# ESP32_with_USBC.net
KiCad netlist of a schematic drawn in Altium Designer
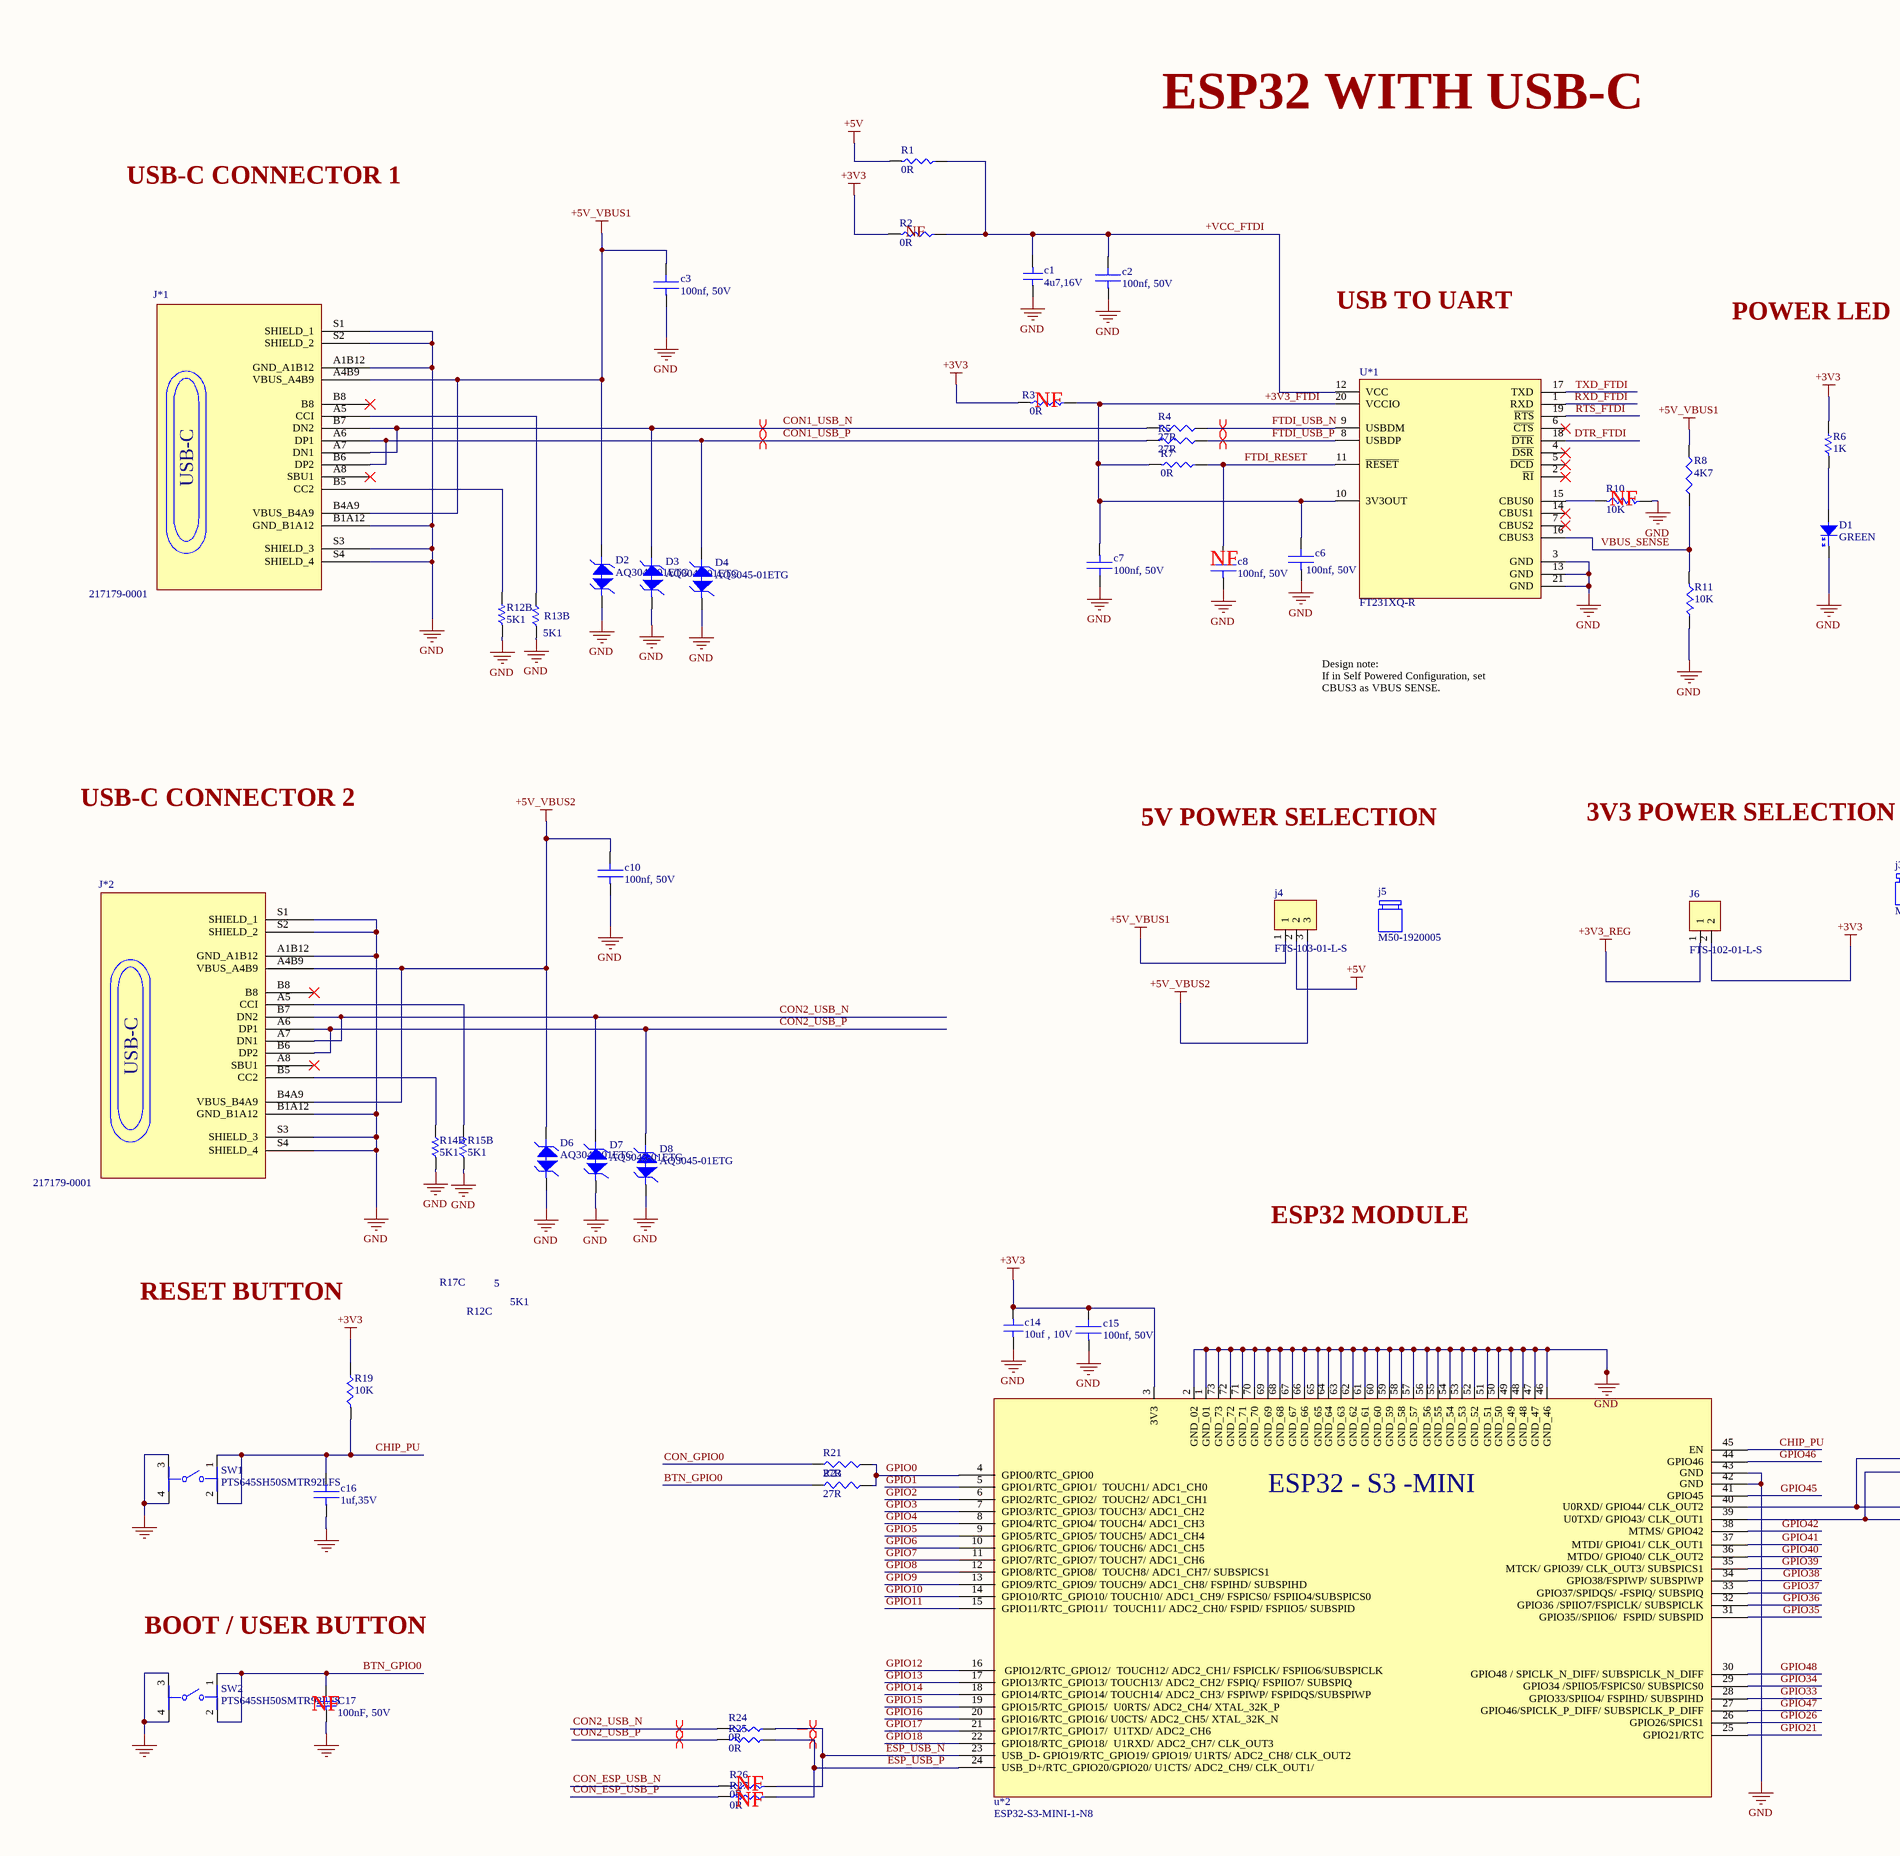
[diagram p0: ESP32 with USBC.SchDoc, left]
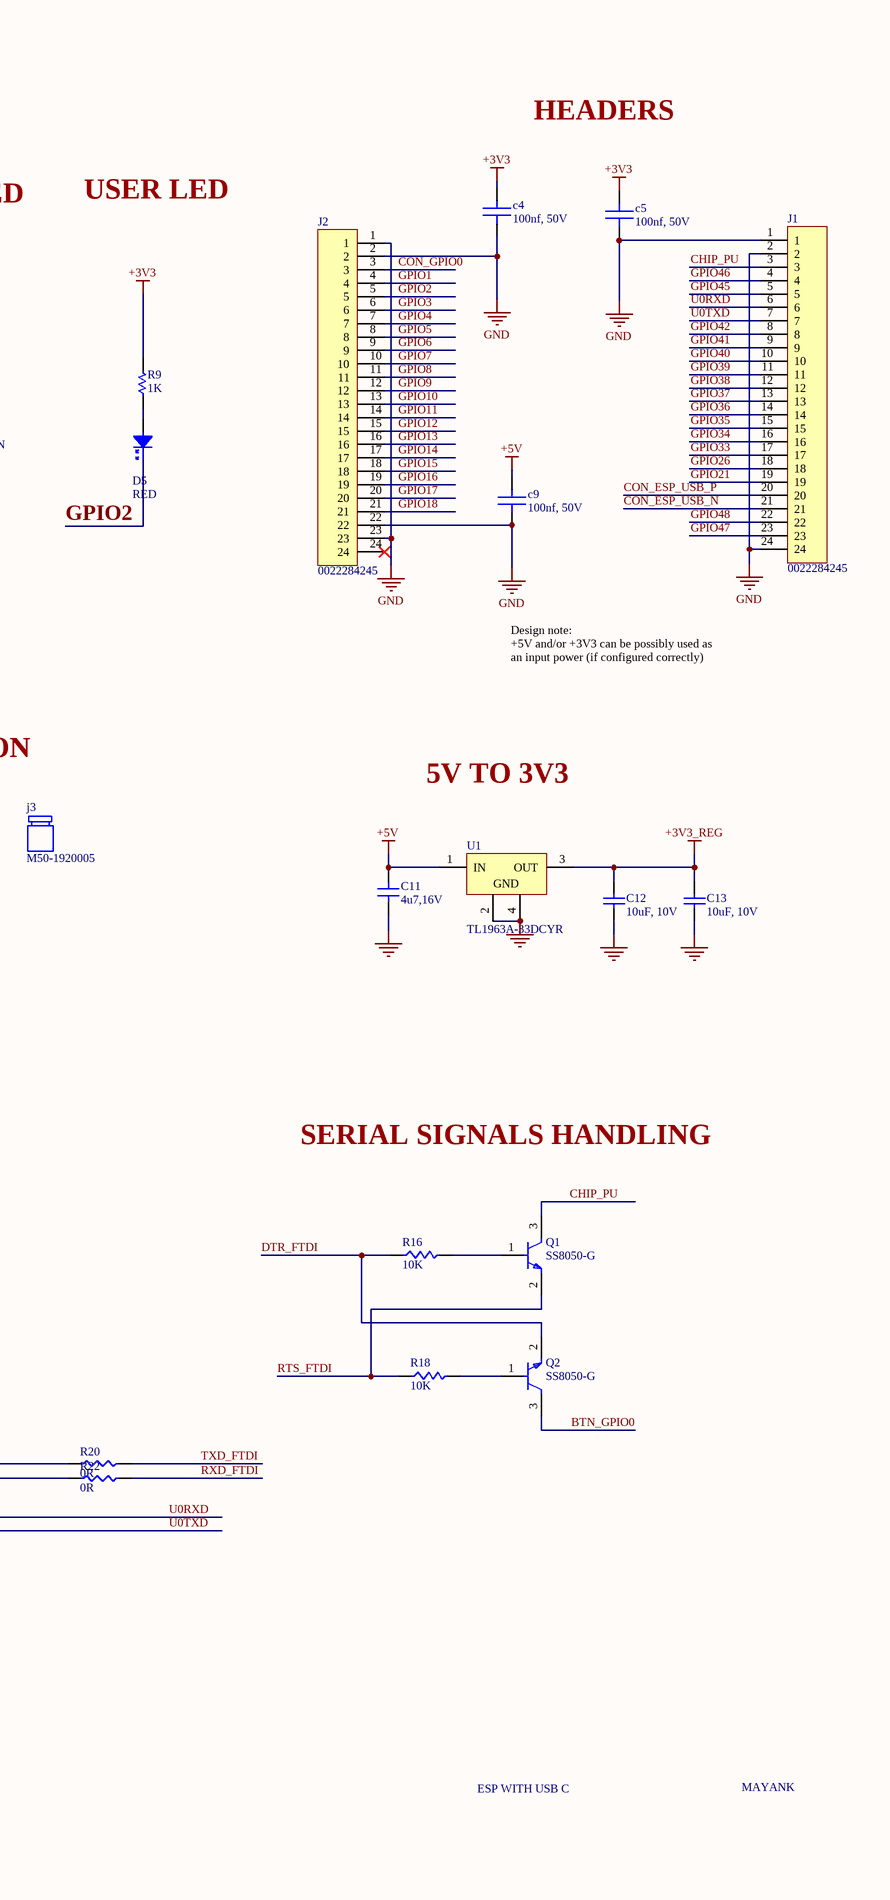
[diagram p1: ESP32 with USBC.SchDoc, right]

(export (version "E")
  (design (tool "Eeschema 10.0.6"))
  (components
    (comp (ref "c1")
      (value "4u7,16V")
      (footprint "CAPC1005X80N")
      (description "CAP CER 4.7UF 16V X5R 0402")
      (fields
        (field (name "MANUFACTURER") "Samsung Electro-Mechanics")
        (field (name "MANUFACTURER PART NUMBER") "CL05A475MO5NUNC")
      )
      (libsource (lib "Schlib1") (part "CL05A475MO5NUNC"))
    )
    (comp (ref "c2")
      (value "100nf, 50V")
      (footprint "CAPC1005X80N")
      (description "50V 100nF X7R 卤10% 0402 Multilayer Ceramic Capacitors MLCC - SMD/SMT ROHS")
      (fields
        (field (name "MANUFACTURER") "Samsung Electro-Mechanics")
        (field (name "MANUFACTURER PART NUMBER") "CL05B104KB5NNNC")
      )
      (libsource (lib "Schlib1") (part "CL05B104KB5NNNC"))
    )
    (comp (ref "c3")
      (value "100nf, 50V")
      (footprint "CAPC1005X80N")
      (description "50V 100nF X7R 卤10% 0402 Multilayer Ceramic Capacitors MLCC - SMD/SMT ROHS")
      (fields
        (field (name "MANUFACTURER") "Samsung Electro-Mechanics")
        (field (name "MANUFACTURER PART NUMBER") "CL05B104KB5NNNC")
      )
      (libsource (lib "Schlib1") (part "CL05B104KB5NNNC"))
    )
    (comp (ref "c4")
      (value "100nf, 50V")
      (footprint "CAPC1005X80N")
      (description "50V 100nF X7R 卤10% 0402 Multilayer Ceramic Capacitors MLCC - SMD/SMT ROHS")
      (fields
        (field (name "MANUFACTURER") "Samsung Electro-Mechanics")
        (field (name "MANUFACTURER PART NUMBER") "CL05B104KB5NNNC")
      )
      (libsource (lib "Schlib1") (part "CL05B104KB5NNNC"))
    )
    (comp (ref "c5")
      (value "100nf, 50V")
      (footprint "CAPC1005X80N")
      (description "50V 100nF X7R 卤10% 0402 Multilayer Ceramic Capacitors MLCC - SMD/SMT ROHS")
      (fields
        (field (name "MANUFACTURER") "Samsung Electro-Mechanics")
        (field (name "MANUFACTURER PART NUMBER") "CL05B104KB5NNNC")
      )
      (libsource (lib "Schlib1") (part "CL05B104KB5NNNC"))
    )
    (comp (ref "c6")
      (value "100nf, 50V")
      (footprint "CAPC1005X80N")
      (description "50V 100nF X7R 卤10% 0402 Multilayer Ceramic Capacitors MLCC - SMD/SMT ROHS")
      (fields
        (field (name "MANUFACTURER") "Samsung Electro-Mechanics")
        (field (name "MANUFACTURER PART NUMBER") "CL05B104KB5NNNC")
      )
      (libsource (lib "Schlib1") (part "CL05B104KB5NNNC"))
    )
    (comp (ref "c7")
      (value "100nf, 50V")
      (footprint "CAPC1005X80N")
      (description "50V 100nF X7R 卤10% 0402 Multilayer Ceramic Capacitors MLCC - SMD/SMT ROHS")
      (fields
        (field (name "MANUFACTURER") "Samsung Electro-Mechanics")
        (field (name "MANUFACTURER PART NUMBER") "CL05B104KB5NNNC")
      )
      (libsource (lib "Schlib1") (part "CL05B104KB5NNNC"))
    )
    (comp (ref "c8")
      (value "100nf, 50V")
      (footprint "CAPC1005X80N")
      (description "50V 100nF X7R 卤10% 0402 Multilayer Ceramic Capacitors MLCC - SMD/SMT ROHS")
      (fields
        (field (name "MANUFACTURER") "Samsung Electro-Mechanics")
        (field (name "MANUFACTURER PART NUMBER") "CL05B104KB5NNNC")
      )
      (libsource (lib "Schlib1") (part "CL05B104KB5NNNC"))
    )
    (comp (ref "c9")
      (value "100nf, 50V")
      (footprint "CAPC1005X80N")
      (description "50V 100nF X7R 卤10% 0402 Multilayer Ceramic Capacitors MLCC - SMD/SMT ROHS")
      (fields
        (field (name "MANUFACTURER") "Samsung Electro-Mechanics")
        (field (name "MANUFACTURER PART NUMBER") "CL05B104KB5NNNC")
      )
      (libsource (lib "Schlib1") (part "CL05B104KB5NNNC"))
    )
    (comp (ref "c10")
      (value "100nf, 50V")
      (footprint "CAPC1005X80N")
      (description "50V 100nF X7R 卤10% 0402 Multilayer Ceramic Capacitors MLCC - SMD/SMT ROHS")
      (fields
        (field (name "MANUFACTURER") "Samsung Electro-Mechanics")
        (field (name "MANUFACTURER PART NUMBER") "CL05B104KB5NNNC")
      )
      (libsource (lib "Schlib1") (part "CL05B104KB5NNNC"))
    )
    (comp (ref "C11")
      (value "4u7,16V")
      (footprint "CAPC1005X80N")
      (description "CAP CER 4.7UF 16V X5R 0402")
      (fields
        (field (name "MANUFACTURER") "Samsung Electro-Mechanics")
        (field (name "MANUFACTURER PART NUMBER") "CL05A475MO5NUNC")
      )
      (libsource (lib "Schlib1") (part "CL05A475MO5NUNC"))
    )
    (comp (ref "C12")
      (value "10uF, 10V")
      (footprint "CAPC1005X80N")
      (description "CAP CER 10UF 10V X5R 0402")
      (fields
        (field (name "MANUFACTURER") "Samsung")
        (field (name "MANUFACTURER PART NUMBER") "CL05A106MP8NUB8")
      )
      (libsource (lib "Schlib") (part "CL05A106MP8NUB8"))
    )
    (comp (ref "C13")
      (value "10uF, 10V")
      (footprint "CAPC1005X80N")
      (description "CAP CER 10UF 10V X5R 0402")
      (fields
        (field (name "MANUFACTURER") "Samsung")
        (field (name "MANUFACTURER PART NUMBER") "CL05A106MP8NUB8")
      )
      (libsource (lib "Schlib") (part "CL05A106MP8NUB8"))
    )
    (comp (ref "c14")
      (value "10uf , 10V")
      (footprint "CAPC1005X80N")
      (description "10V 10uF X5R 卤20% 0402 Multilayer Ceramic Capacitors MLCC - SMD/SMT ROHS")
      (fields
        (field (name "MANUFACTURER") "Samsung Electro-Mechanics")
        (field (name "MANUFACTURER PART NUMBER") "CL05A106MP6NUN8")
      )
      (libsource (lib "Schlib1") (part "CL05A106MP6NUN8"))
    )
    (comp (ref "c15")
      (value "100nf, 50V")
      (footprint "CAPC1005X80N")
      (description "50V 100nF X7R 卤10% 0402 Multilayer Ceramic Capacitors MLCC - SMD/SMT ROHS")
      (fields
        (field (name "MANUFACTURER") "Samsung Electro-Mechanics")
        (field (name "MANUFACTURER PART NUMBER") "CL05B104KB5NNNC")
      )
      (libsource (lib "Schlib1") (part "CL05B104KB5NNNC"))
    )
    (comp (ref "c16")
      (value "1uf,35V")
      (footprint "CAPC1005X80N")
      (description "CAP CER 1UF 35V X5R 0402")
      (fields
        (field (name "MANUFACTURER") "Samsung Electro-Mechanics")
        (field (name "MANUFACTURER PART NUMBER") "CL05A105KL5NRNC")
      )
      (libsource (lib "Schlib1") (part "CL05A105KL5NRNC"))
    )
    (comp (ref "C17")
      (value "100nF, 50V")
      (footprint "CAPC1005X80N")
      (description "CAP CER 0.1UF 50V X7R 0402")
      (fields
        (field (name "MANUFACTURER") "Samsung")
        (field (name "MANUFACTURER PART NUMBER") "CL05B104KB54PNC")
      )
      (libsource (lib "Schlib") (part "CL05B104KB54PNC"))
    )
    (comp (ref "D1")
      (value "GREEN")
      (footprint "LED0402G")
      (description "Chipled (0402) Truegreen Ultrabright -E4 ¦Vishay VLMTG1500-GS08")
      (fields
        (field (name "MANUFACTURER") "Vishay")
        (field (name "MANUFACTURER PART NUMBER") "VLMTG1500-GS08")
      )
      (libsource (lib "Schlib1") (part "VLMTG1500-GS08"))
    )
    (comp (ref "D2")
      (value "AQ3045-01ETG")
      (footprint "SOD882")
      (description "TVS DIODE 5.3VWM 12VC SOD882")
      (fields (field (name "MANUFACTURER") "Littelfuse") (field (name "LCSC PART NUMBER") "C3710326"))
      (libsource (lib "Schlib1") (part "AQ3045-01ETG"))
    )
    (comp (ref "D3")
      (value "AQ3045-01ETG")
      (footprint "SOD882")
      (description "TVS DIODE 5.3VWM 12VC SOD882")
      (fields (field (name "MANUFACTURER") "Littelfuse") (field (name "LCSC PART NUMBER") "C3710326"))
      (libsource (lib "Schlib1") (part "AQ3045-01ETG"))
    )
    (comp (ref "D4")
      (value "AQ3045-01ETG")
      (footprint "SOD882")
      (description "TVS DIODE 5.3VWM 12VC SOD882")
      (fields (field (name "MANUFACTURER") "Littelfuse") (field (name "LCSC PART NUMBER") "C3710326"))
      (libsource (lib "Schlib1") (part "AQ3045-01ETG"))
    )
    (comp (ref "D5")
      (value "RED")
      (footprint "LED0402R")
      (description "LED Uni-Color Super Red 639nm 2-Pin Chip 0402(1006Metric) T/R")
      (fields
        (field (name "MANUFACTURER") "Vishay")
        (field (name "MANUFACTURER PART NUMBER") "VLMS1500-GS08")
      )
      (libsource (lib "Schlib1") (part "VLMS1500-GS08"))
    )
    (comp (ref "D6")
      (value "AQ3045-01ETG")
      (footprint "SOD882")
      (description "TVS DIODE 5.3VWM 12VC SOD882")
      (fields (field (name "MANUFACTURER") "Littelfuse") (field (name "LCSC PART NUMBER") "C3710326"))
      (libsource (lib "Schlib1") (part "AQ3045-01ETG"))
    )
    (comp (ref "D7")
      (value "AQ3045-01ETG")
      (footprint "SOD882")
      (description "TVS DIODE 5.3VWM 12VC SOD882")
      (fields (field (name "MANUFACTURER") "Littelfuse") (field (name "LCSC PART NUMBER") "C3710326"))
      (libsource (lib "Schlib1") (part "AQ3045-01ETG"))
    )
    (comp (ref "D8")
      (value "AQ3045-01ETG")
      (footprint "SOD882")
      (description "TVS DIODE 5.3VWM 12VC SOD882")
      (fields (field (name "MANUFACTURER") "Littelfuse") (field (name "LCSC PART NUMBER") "C3710326"))
      (libsource (lib "Schlib1") (part "AQ3045-01ETG"))
    )
    (comp (ref "J*1")
      (value "217179-0001")
      (footprint "FP-2171790001-MFG")
      (description "CONN RCP USB2.0 TYP C 24P SMD RA")
      (fields (field (name "MANUFACTURER") "Molex") (field (name "LCSC PART NUMBER") "C3197684"))
      (libsource (lib "Schlib1") (part "217179-0001"))
    )
    (comp (ref "J*2")
      (value "217179-0001")
      (footprint "FP-2171790001-MFG")
      (description "CONN RCP USB2.0 TYP C 24P SMD RA")
      (fields (field (name "MANUFACTURER") "Molex") (field (name "LCSC PART NUMBER") "C3197684"))
      (libsource (lib "Schlib1") (part "217179-0001"))
    )
    (comp (ref "J1")
      (value "0022284245")
      (footprint "HDR_1X24_2.54MM")
      (description "CONN HEADER VERT 24POS 2.54MM")
      (fields (field (name "MANUFACTURER") "Molex") (field (name "LCSC PART NUMBER") "C7145888"))
      (libsource (lib "") (part "0022284245_1"))
    )
    (comp (ref "J2")
      (value "0022284245")
      (footprint "HDR_1X24_2.54MM")
      (description "CONN HEADER VERT 24POS 2.54MM")
      (fields (field (name "MANUFACTURER") "Molex") (field (name "LCSC PART NUMBER") "C7145888"))
      (libsource (lib "Schlib") (part "0022284245"))
    )
    (comp (ref "j3")
      (value "M50-1920005")
      (description "CONN SHUNT 1.27MM RED")
      (fields (field (name "MANUFACTURER") "Harwin") (field (name "LCSC PART NUMBER") "C6985646"))
      (libsource (lib "Schlib1") (part "M50-1920005"))
    )
    (comp (ref "j4")
      (value "FTS-103-01-L-S")
      (footprint "HDR_1X3_1.27")
      (description "CONN HEADER VERT 3POS 1.27MM")
      (fields (field (name "MANUFACTURER") "Samtec") (field (name "LCSC PART NUMBER") "C6253705"))
      (libsource (lib "Schlib1") (part "FTS-103-01-L-S"))
    )
    (comp (ref "j5")
      (value "M50-1920005")
      (description "CONN SHUNT 1.27MM RED")
      (fields (field (name "MANUFACTURER") "Harwin") (field (name "LCSC PART NUMBER") "C6985646"))
      (libsource (lib "Schlib1") (part "M50-1920005"))
    )
    (comp (ref "J6")
      (value "FTS-102-01-L-S")
      (footprint "HDR_1X3_1.27MM")
      (description "CONN HEADER VERT 2POS 1.27MM")
      (fields (field (name "MANUFACTURER") "Samtec") (field (name "LCSC PART NUMBER") "C7194937"))
      (libsource (lib "Schlib1") (part "FTS-102-01-L-S"))
    )
    (comp (ref "Q1")
      (value "SS8050-G")
      (footprint "FP-SS8050-G-IPC_A")
      (fields (field (name "MANUFACTURER") "Comchip") (field (name "LCSC PART NUMBER") "C3199946"))
      (libsource (lib "Schlib1") (part "SS8050-G"))
    )
    (comp (ref "Q2")
      (value "SS8050-G")
      (footprint "FP-SS8050-G-IPC_A")
      (fields (field (name "MANUFACTURER") "Comchip") (field (name "LCSC PART NUMBER") "C3199946"))
      (libsource (lib "Schlib1") (part "SS8050-G"))
    )
    (comp (ref "R1")
      (value "0R")
      (footprint "RESC1005X37N")
      (description "RES 0 OHM JUMPER 1/16W 0402")
      (fields
        (field (name "MANUFACTURER") "Yageo Group")
        (field (name "MANUFACTURER PART NUMBER") "RC0402JR-070RL")
      )
      (libsource (lib "Schlib1") (part "RC0402JR-070RL"))
    )
    (comp (ref "R2")
      (value "0R")
      (footprint "RESC1005X37N")
      (description "RES 0 OHM JUMPER 1/16W 0402")
      (fields
        (field (name "MANUFACTURER") "Yageo Group")
        (field (name "MANUFACTURER PART NUMBER") "RC0402JR-070RL")
      )
      (libsource (lib "Schlib1") (part "RC0402JR-070RL"))
    )
    (comp (ref "R3")
      (value "0R")
      (footprint "RESC1005X37N")
      (description "RES 0 OHM JUMPER 1/16W 0402")
      (fields
        (field (name "MANUFACTURER") "Yageo Group")
        (field (name "MANUFACTURER PART NUMBER") "RC0402JR-070RL")
      )
      (libsource (lib "Schlib1") (part "RC0402JR-070RL"))
    )
    (comp (ref "R4")
      (value "27R")
      (footprint "RESC1005X37N")
      (description "RES 27 OHM 1% 1/16W 0402")
      (fields
        (field (name "MANUFACTURER") "Yageo")
        (field (name "MANUFACTURER PART NUMBER") "RC0402FR-0727RL")
      )
      (libsource (lib "Schlib") (part "RC0402FR-0727RL"))
    )
    (comp (ref "R5")
      (value "27R")
      (footprint "RESC1005X37N")
      (description "RES 27 OHM 1% 1/16W 0402")
      (fields
        (field (name "MANUFACTURER") "Yageo")
        (field (name "MANUFACTURER PART NUMBER") "RC0402FR-0727RL")
      )
      (libsource (lib "Schlib") (part "RC0402FR-0727RL"))
    )
    (comp (ref "R6")
      (value "1K")
      (footprint "RESC1005X37N")
      (description "RES 1K OHM 1% 1/16W 0402")
      (fields
        (field (name "MANUFACTURER") "Yageo Group")
        (field (name "MANUFACTURER PART NUMBER") "RC0402FR-071KL")
      )
      (libsource (lib "Schlib1") (part "RC0402FR-071KL"))
    )
    (comp (ref "R7")
      (value "0R")
      (footprint "RESC1005X37N")
      (description "RES 0 OHM JUMPER 1/16W 0402")
      (fields
        (field (name "MANUFACTURER") "Yageo Group")
        (field (name "MANUFACTURER PART NUMBER") "RC0402JR-070RL")
      )
      (libsource (lib "Schlib1") (part "RC0402JR-070RL"))
    )
    (comp (ref "R8")
      (value "4K7")
      (footprint "RESC1005X37N")
      (description "RES 4.7K OHM 1% 1/16W 0402")
      (fields
        (field (name "MANUFACTURER") "Yageo")
        (field (name "MANUFACTURER PART NUMBER") "RC0402FR-074K7L")
      )
      (libsource (lib "Schlib") (part "RC0402FR-074K7L"))
    )
    (comp (ref "R9")
      (value "1K")
      (footprint "RESC1005X37N")
      (description "RES 1K OHM 1% 1/16W 0402")
      (fields
        (field (name "MANUFACTURER") "Yageo Group")
        (field (name "MANUFACTURER PART NUMBER") "RC0402FR-071KL")
      )
      (libsource (lib "Schlib1") (part "RC0402FR-071KL"))
    )
    (comp (ref "R10")
      (value "10K")
      (footprint "RESC1005X37N")
      (description "RES SMD 10K OHM 1% 1/16W 0402")
      (fields
        (field (name "MANUFACTURER") "Yageo Group")
        (field (name "MANUFACTURER PART NUMBER") "AC0402FR-0710KL")
      )
      (libsource (lib "Schlib1") (part "AC0402FR-0710KL"))
    )
    (comp (ref "R11")
      (value "10K")
      (footprint "RESC1005X37N")
      (description "RES SMD 10K OHM 1% 1/16W 0402")
      (fields
        (field (name "MANUFACTURER") "Yageo Group")
        (field (name "MANUFACTURER PART NUMBER") "AC0402FR-0710KL")
      )
      (libsource (lib "Schlib1") (part "AC0402FR-0710KL"))
    )
    (comp (ref "R12")
      (value "5K1")
      (footprint "RESC1005X37N")
      (description "Res Thick Film 0402 5.1K Ohm 1% 0.063W(1/16W) ±100ppm/°C Pad SMD T/R Automotive AEC-Q200")
      (fields
        (field (name "MANUFACTURER") "Yageo Group")
        (field (name "MANUFACTURER PART NUMBER") "AC0402FR-135K1L")
      )
      (libsource (lib "Schlib1") (part "AC0402FR-135K1L"))
    )
    (comp (ref "R13")
      (value "5K1")
      (footprint "RESC1005X37N")
      (description "Res Thick Film 0402 5.1K Ohm 1% 0.063W(1/16W) ±100ppm/°C Pad SMD T/R Automotive AEC-Q200")
      (fields
        (field (name "MANUFACTURER") "Yageo Group")
        (field (name "MANUFACTURER PART NUMBER") "AC0402FR-135K1L")
      )
      (libsource (lib "Schlib1") (part "AC0402FR-135K1L"))
    )
    (comp (ref "R14")
      (value "5K1")
      (footprint "RESC1005X37N")
      (description "Res Thick Film 0402 5.1K Ohm 1% 0.063W(1/16W) ±100ppm/°C Pad SMD T/R Automotive AEC-Q200")
      (fields
        (field (name "MANUFACTURER") "Yageo Group")
        (field (name "MANUFACTURER PART NUMBER") "AC0402FR-135K1L")
      )
      (libsource (lib "Schlib1") (part "AC0402FR-135K1L"))
    )
    (comp (ref "R15")
      (value "5K1")
      (footprint "RESC1005X37N")
      (description "Res Thick Film 0402 5.1K Ohm 1% 0.063W(1/16W) ±100ppm/°C Pad SMD T/R Automotive AEC-Q200")
      (fields
        (field (name "MANUFACTURER") "Yageo Group")
        (field (name "MANUFACTURER PART NUMBER") "AC0402FR-135K1L")
      )
      (libsource (lib "Schlib1") (part "AC0402FR-135K1L"))
    )
    (comp (ref "R16")
      (value "10K")
      (footprint "RESC1005X37N")
      (description "RES SMD 10K OHM 1% 1/16W 0402")
      (fields
        (field (name "MANUFACTURER") "Yageo Group")
        (field (name "MANUFACTURER PART NUMBER") "AC0402FR-0710KL")
      )
      (libsource (lib "Schlib1") (part "AC0402FR-0710KL"))
    )
    (comp (ref "R17")
      (value "5")
      (footprint "RESC1005X37N")
      (description "Res Thick Film 0402 5.1K Ohm 1% 0.063W(1/16W) ±100ppm/°C Pad SMD T/R Automotive AEC-Q200")
      (fields
        (field (name "MANUFACTURER") "Yageo Group")
        (field (name "MANUFACTURER PART NUMBER") "AC0402FR-135K1L")
      )
      (libsource (lib "Schlib1") (part "AC0402FR-135K1L"))
    )
    (comp (ref "R18")
      (value "10K")
      (footprint "RESC1005X37N")
      (description "RES SMD 10K OHM 1% 1/16W 0402")
      (fields
        (field (name "MANUFACTURER") "Yageo Group")
        (field (name "MANUFACTURER PART NUMBER") "AC0402FR-0710KL")
      )
      (libsource (lib "Schlib1") (part "AC0402FR-0710KL"))
    )
    (comp (ref "R19")
      (value "10K")
      (footprint "RESC1005X37N")
      (description "RES SMD 10K OHM 1% 1/16W 0402")
      (fields
        (field (name "MANUFACTURER") "Yageo Group")
        (field (name "MANUFACTURER PART NUMBER") "AC0402FR-0710KL")
      )
      (libsource (lib "Schlib1") (part "AC0402FR-0710KL"))
    )
    (comp (ref "R20")
      (value "0R")
      (footprint "RESC1005X37N")
      (description "RES 0 OHM JUMPER 1/16W 0402")
      (fields
        (field (name "MANUFACTURER") "Yageo Group")
        (field (name "MANUFACTURER PART NUMBER") "RC0402JR-070RL")
      )
      (libsource (lib "Schlib1") (part "RC0402JR-070RL"))
    )
    (comp (ref "R21")
      (value "27R")
      (footprint "RESC1005X37N")
      (description "RES 27 OHM 1% 1/16W 0402")
      (fields
        (field (name "MANUFACTURER") "Yageo")
        (field (name "MANUFACTURER PART NUMBER") "RC0402FR-0727RL")
      )
      (libsource (lib "Schlib") (part "RC0402FR-0727RL"))
    )
    (comp (ref "R22")
      (value "0R")
      (footprint "RESC1005X37N")
      (description "RES 0 OHM JUMPER 1/16W 0402")
      (fields
        (field (name "MANUFACTURER") "Yageo Group")
        (field (name "MANUFACTURER PART NUMBER") "RC0402JR-070RL")
      )
      (libsource (lib "Schlib1") (part "RC0402JR-070RL"))
    )
    (comp (ref "R23")
      (value "27R")
      (footprint "RESC1005X37N")
      (description "RES 27 OHM 1% 1/16W 0402")
      (fields
        (field (name "MANUFACTURER") "Yageo")
        (field (name "MANUFACTURER PART NUMBER") "RC0402FR-0727RL")
      )
      (libsource (lib "Schlib") (part "RC0402FR-0727RL"))
    )
    (comp (ref "R24")
      (value "0R")
      (footprint "RESC1005X37N")
      (description "RES 0 OHM JUMPER 1/16W 0402")
      (fields
        (field (name "MANUFACTURER") "Yageo Group")
        (field (name "MANUFACTURER PART NUMBER") "RC0402JR-070RL")
      )
      (libsource (lib "Schlib1") (part "RC0402JR-070RL"))
    )
    (comp (ref "R25")
      (value "0R")
      (footprint "RESC1005X37N")
      (description "RES 0 OHM JUMPER 1/16W 0402")
      (fields
        (field (name "MANUFACTURER") "Yageo Group")
        (field (name "MANUFACTURER PART NUMBER") "RC0402JR-070RL")
      )
      (libsource (lib "Schlib1") (part "RC0402JR-070RL"))
    )
    (comp (ref "R26")
      (value "0R")
      (footprint "RESC1005X37N")
      (description "RES 0 OHM JUMPER 1/16W 0402")
      (fields
        (field (name "MANUFACTURER") "Yageo Group")
        (field (name "MANUFACTURER PART NUMBER") "RC0402JR-070RL")
      )
      (libsource (lib "Schlib1") (part "RC0402JR-070RL"))
    )
    (comp (ref "R27")
      (value "0R")
      (footprint "RESC1005X37N")
      (description "RES 0 OHM JUMPER 1/16W 0402")
      (fields
        (field (name "MANUFACTURER") "Yageo Group")
        (field (name "MANUFACTURER PART NUMBER") "RC0402JR-070RL")
      )
      (libsource (lib "Schlib1") (part "RC0402JR-070RL"))
    )
    (comp (ref "SW1")
      (value "PTS645SH50SMTR92LFS")
      (footprint "FP-PTS645SH50SMTR92LFS-MFG")
      (description "SWITCH TACTILE SPST-NO 0.05A 12V")
      (fields (field (name "MANUFACTURER") "C&K Components") (field (name "LCSC PART NUMBER") "C221869"))
      (libsource (lib "Schlib1") (part "PTS645SH50SMTR92LFS"))
    )
    (comp (ref "SW2")
      (value "PTS645SH50SMTR92LFS")
      (footprint "FP-PTS645SH50SMTR92LFS-MFG")
      (description "SWITCH TACTILE SPST-NO 0.05A 12V")
      (fields (field (name "MANUFACTURER") "C&K Components") (field (name "LCSC PART NUMBER") "C221869"))
      (libsource (lib "Schlib1") (part "PTS645SH50SMTR92LFS"))
    )
    (comp (ref "U*1")
      (value "FT231XQ-R")
      (footprint "FP-QFN-20-IPC_B")
      (description "IC USB SERIAL FULL UART 20QFN")
      (fields (field (name "MANUFACTURER") "FTDI") (field (name "LCSC PART NUMBER") "C132159"))
      (libsource (lib "Schlib1") (part "FT231XQ-R"))
    )
    (comp (ref "u*2")
      (value "ESP32-S3-MINI-1-N8")
      (footprint "XCVR_ESP32-S3-MINI-1-N8")
      (description "SMD module, ESP32-S3FN8, 8 MB SPI flash, PCB antenna")
      (fields (field (name "MANUFACTURER") "Espressif Systems") (field (name "LCSC PART NUMBER") "C2913206"))
      (libsource (lib "Schlib1") (part "ESP32-S3-MINI-1-N8"))
    )
    (comp (ref "U1")
      (value "TL1963A-33DCYR")
      (footprint "DCY0004A_L")
      (description "IC REG LIN 3.3V 1.5A SOT-223-4")
      (fields (field (name "MANUFACTURER") "Texas Instruments") (field (name "LCSC PART NUMBER") "C181262"))
      (libsource (lib "Schlib1") (part "TL1963A-33DCYR"))
    )
  )
  (nets
    (net (code "1") (name "+3V3") (class "Default")
      (node (ref "J6") (pin "2") (pinfunction "2_2") (pintype "passive"))
      (node (ref "R19") (pin "2") (pinfunction "2_2") (pintype "passive"))
      (node (ref "R2") (pin "1") (pinfunction "1_1") (pintype "passive"))
      (node (ref "R3") (pin "1") (pinfunction "1_1") (pintype "passive"))
      (node (ref "R6") (pin "2") (pinfunction "2_2") (pintype "passive"))
      (node (ref "R9") (pin "2") (pinfunction "2_2") (pintype "passive"))
      (node (ref "c14") (pin "2") (pinfunction "2_2") (pintype "passive"))
      (node (ref "c15") (pin "2") (pinfunction "2_2") (pintype "passive"))
      (node (ref "c4") (pin "2") (pinfunction "2_2") (pintype "passive"))
      (node (ref "c5") (pin "2") (pinfunction "2_2") (pintype "passive"))
      (node (ref "u*2") (pin "3") (pinfunction "3V3_3") (pintype "passive"))
    )
    (net (code "2") (name "+3V3_REG") (class "Default")
      (node (ref "C12") (pin "2") (pinfunction "2_2") (pintype "passive"))
      (node (ref "C13") (pin "2") (pinfunction "2_2") (pintype "passive"))
      (node (ref "J6") (pin "1") (pinfunction "1_1") (pintype "passive"))
      (node (ref "U1") (pin "3") (pinfunction "OUT_3") (pintype "power_in"))
    )
    (net (code "3") (name "+5V") (class "Default")
      (node (ref "C11") (pin "2") (pinfunction "2_2") (pintype "passive"))
      (node (ref "R1") (pin "1") (pinfunction "1_1") (pintype "passive"))
      (node (ref "U1") (pin "1") (pinfunction "IN_1") (pintype "power_in"))
      (node (ref "c9") (pin "2") (pinfunction "2_2") (pintype "passive"))
      (node (ref "j4") (pin "2") (pinfunction "2_2") (pintype "passive"))
    )
    (net (code "4") (name "+5V_VBUS1") (class "Default")
      (node (ref "D2") (pin "2") (pinfunction "2_2") (pintype "passive"))
      (node (ref "J*1") (pin "A4B9") (pinfunction "VBUS_A4B9_A4B9") (pintype "passive"))
      (node (ref "J*1") (pin "B4A9") (pinfunction "VBUS_B4A9_B4A9") (pintype "passive"))
      (node (ref "R8") (pin "2") (pinfunction "2_2") (pintype "passive"))
      (node (ref "c3") (pin "2") (pinfunction "2_2") (pintype "passive"))
      (node (ref "j4") (pin "1") (pinfunction "1_1") (pintype "passive"))
    )
    (net (code "5") (name "+5V_VBUS2") (class "Default")
      (node (ref "D6") (pin "2") (pinfunction "2_2") (pintype "passive"))
      (node (ref "J*2") (pin "A4B9") (pinfunction "VBUS_A4B9_A4B9") (pintype "passive"))
      (node (ref "J*2") (pin "B4A9") (pinfunction "VBUS_B4A9_B4A9") (pintype "passive"))
      (node (ref "c10") (pin "2") (pinfunction "2_2") (pintype "passive"))
      (node (ref "j4") (pin "3") (pinfunction "3_3") (pintype "passive"))
    )
    (net (code "6") (name "/+3V3_FTDI") (class "Default")
      (node (ref "R3") (pin "2") (pinfunction "2_2") (pintype "passive"))
      (node (ref "R7") (pin "1") (pinfunction "1_1") (pintype "passive"))
      (node (ref "U*1") (pin "10") (pinfunction "3V3OUT_10") (pintype "passive"))
      (node (ref "U*1") (pin "20") (pinfunction "VCCIO_20") (pintype "passive"))
      (node (ref "c6") (pin "2") (pinfunction "2_2") (pintype "passive"))
      (node (ref "c7") (pin "1") (pinfunction "1_1") (pintype "passive"))
    )
    (net (code "7") (name "/+VCC_FTDI") (class "Default")
      (node (ref "R1") (pin "2") (pinfunction "2_2") (pintype "passive"))
      (node (ref "R2") (pin "2") (pinfunction "2_2") (pintype "passive"))
      (node (ref "U*1") (pin "12") (pinfunction "VCC_12") (pintype "passive"))
      (node (ref "c1") (pin "2") (pinfunction "2_2") (pintype "passive"))
      (node (ref "c2") (pin "2") (pinfunction "2_2") (pintype "passive"))
    )
    (net (code "8") (name "/BTN_GPIO0") (class "Default")
      (node (ref "C17") (pin "2") (pinfunction "2_2") (pintype "passive"))
      (node (ref "Q2") (pin "3") (pinfunction "C_3") (pintype "passive"))
      (node (ref "R23") (pin "1") (pinfunction "1_1") (pintype "passive"))
      (node (ref "SW2") (pin "1") (pinfunction "1_1") (pintype "passive"))
      (node (ref "SW2") (pin "2") (pinfunction "2_2") (pintype "passive"))
    )
    (net (code "9") (name "/CHIP_PU") (class "Default")
      (node (ref "J1") (pin "3") (pinfunction "3_3") (pintype "passive"))
      (node (ref "Q1") (pin "3") (pinfunction "C_3") (pintype "passive"))
      (node (ref "R19") (pin "1") (pinfunction "1_1") (pintype "passive"))
      (node (ref "SW1") (pin "1") (pinfunction "1_1") (pintype "passive"))
      (node (ref "SW1") (pin "2") (pinfunction "2_2") (pintype "passive"))
      (node (ref "c16") (pin "2") (pinfunction "2_2") (pintype "passive"))
      (node (ref "u*2") (pin "45") (pinfunction "EN_45") (pintype "passive"))
    )
    (net (code "10") (name "/CON1_USB_N") (class "Default")
      (node (ref "D3") (pin "2") (pinfunction "2_2") (pintype "passive"))
      (node (ref "J*1") (pin "A7") (pinfunction "DN1_A7") (pintype "passive"))
      (node (ref "J*1") (pin "B7") (pinfunction "DN2_B7") (pintype "passive"))
      (node (ref "R4") (pin "1") (pinfunction "1_1") (pintype "passive"))
    )
    (net (code "11") (name "/CON1_USB_P") (class "Default")
      (node (ref "D4") (pin "2") (pinfunction "2_2") (pintype "passive"))
      (node (ref "J*1") (pin "A6") (pinfunction "DP1_A6") (pintype "passive"))
      (node (ref "J*1") (pin "B6") (pinfunction "DP2_B6") (pintype "passive"))
      (node (ref "R5") (pin "1") (pinfunction "1_1") (pintype "passive"))
    )
    (net (code "12") (name "/CON2_USB_N") (class "Default")
      (node (ref "D7") (pin "2") (pinfunction "2_2") (pintype "passive"))
      (node (ref "J*2") (pin "A7") (pinfunction "DN1_A7") (pintype "passive"))
      (node (ref "J*2") (pin "B7") (pinfunction "DN2_B7") (pintype "passive"))
      (node (ref "R24") (pin "1") (pinfunction "1_1") (pintype "passive"))
    )
    (net (code "13") (name "/CON2_USB_P") (class "Default")
      (node (ref "D8") (pin "2") (pinfunction "2_2") (pintype "passive"))
      (node (ref "J*2") (pin "A6") (pinfunction "DP1_A6") (pintype "passive"))
      (node (ref "J*2") (pin "B6") (pinfunction "DP2_B6") (pintype "passive"))
      (node (ref "R25") (pin "1") (pinfunction "1_1") (pintype "passive"))
    )
    (net (code "14") (name "/CON_ESP_USB_N") (class "Default")
      (node (ref "J1") (pin "21") (pinfunction "21_21") (pintype "passive"))
      (node (ref "R26") (pin "1") (pinfunction "1_1") (pintype "passive"))
    )
    (net (code "15") (name "/CON_ESP_USB_P") (class "Default")
      (node (ref "J1") (pin "20") (pinfunction "20_20") (pintype "passive"))
      (node (ref "R27") (pin "1") (pinfunction "1_1") (pintype "passive"))
    )
    (net (code "16") (name "/CON_GPIO0") (class "Default")
      (node (ref "J2") (pin "3") (pinfunction "3_3") (pintype "passive"))
      (node (ref "R21") (pin "1") (pinfunction "1_1") (pintype "passive"))
    )
    (net (code "17") (name "/DTR_FTDI") (class "Default")
      (node (ref "Q2") (pin "2") (pinfunction "E_2") (pintype "passive"))
      (node (ref "R16") (pin "1") (pinfunction "1_1") (pintype "passive"))
      (node (ref "U*1") (pin "18") (pinfunction "~{DTR}_18") (pintype "passive"))
    )
    (net (code "18") (name "/ESP_USB_N") (class "Default")
      (node (ref "R24") (pin "2") (pinfunction "2_2") (pintype "passive"))
      (node (ref "R26") (pin "2") (pinfunction "2_2") (pintype "passive"))
      (node (ref "u*2") (pin "23") (pinfunction "USB_D-_GPIO19/RTC_GPIO19/_GPIO19/_U1RTS/_ADC2_CH8/_CLK_OUT2_23") (pintype "passive"))
    )
    (net (code "19") (name "/ESP_USB_P") (class "Default")
      (node (ref "R25") (pin "2") (pinfunction "2_2") (pintype "passive"))
      (node (ref "R27") (pin "2") (pinfunction "2_2") (pintype "passive"))
      (node (ref "u*2") (pin "24") (pinfunction "USB_D+/RTC_GPIO20/GPIO20/_U1CTS/_ADC2_CH9/_CLK_OUT1/_24") (pintype "passive"))
    )
    (net (code "20") (name "/FTDI_RESET") (class "Default")
      (node (ref "R7") (pin "2") (pinfunction "2_2") (pintype "passive"))
      (node (ref "U*1") (pin "11") (pinfunction "~{RESET}_11") (pintype "passive"))
      (node (ref "c8") (pin "2") (pinfunction "2_2") (pintype "passive"))
    )
    (net (code "21") (name "/FTDI_USB_N") (class "Default")
      (node (ref "R4") (pin "2") (pinfunction "2_2") (pintype "passive"))
      (node (ref "U*1") (pin "9") (pinfunction "USBDM_9") (pintype "passive"))
    )
    (net (code "22") (name "/FTDI_USB_P") (class "Default")
      (node (ref "R5") (pin "2") (pinfunction "2_2") (pintype "passive"))
      (node (ref "U*1") (pin "8") (pinfunction "USBDP_8") (pintype "passive"))
    )
    (net (code "23") (name "/GPIO0") (class "Default")
      (node (ref "R21") (pin "2") (pinfunction "2_2") (pintype "passive"))
      (node (ref "R23") (pin "2") (pinfunction "2_2") (pintype "passive"))
      (node (ref "u*2") (pin "4") (pinfunction "GPIO0/RTC_GPIO0_4") (pintype "passive"))
    )
    (net (code "24") (name "/GPIO1") (class "Default")
      (node (ref "J2") (pin "4") (pinfunction "4_4") (pintype "passive"))
      (node (ref "u*2") (pin "5") (pinfunction "GPIO1/RTC_GPIO1/__TOUCH1/_ADC1_CH0_5") (pintype "passive"))
    )
    (net (code "25") (name "/GPIO2") (class "Default")
      (node (ref "D5") (pin "1") (pinfunction "1_1") (pintype "passive"))
      (node (ref "J2") (pin "5") (pinfunction "5_5") (pintype "passive"))
      (node (ref "u*2") (pin "6") (pinfunction "GPIO2/RTC_GPIO2/__TOUCH2/_ADC1_CH1_6") (pintype "passive"))
    )
    (net (code "26") (name "/GPIO3") (class "Default")
      (node (ref "J2") (pin "6") (pinfunction "6_6") (pintype "passive"))
      (node (ref "u*2") (pin "7") (pinfunction "GPIO3/RTC_GPIO3/_TOUCH3/_ADC1_CH2_7") (pintype "passive"))
    )
    (net (code "27") (name "/GPIO4") (class "Default")
      (node (ref "J2") (pin "7") (pinfunction "7_7") (pintype "passive"))
      (node (ref "u*2") (pin "8") (pinfunction "GPIO4/RTC_GPIO4/_TOUCH4/_ADC1_CH3_8") (pintype "passive"))
    )
    (net (code "28") (name "/GPIO5") (class "Default")
      (node (ref "J2") (pin "8") (pinfunction "8_8") (pintype "passive"))
      (node (ref "u*2") (pin "9") (pinfunction "GPIO5/RTC_GPIO5/_TOUCH5/_ADC1_CH4_9") (pintype "passive"))
    )
    (net (code "29") (name "/GPIO6") (class "Default")
      (node (ref "J2") (pin "9") (pinfunction "9_9") (pintype "passive"))
      (node (ref "u*2") (pin "10") (pinfunction "GPIO6/RTC_GPIO6/_TOUCH6/_ADC1_CH5_10") (pintype "passive"))
    )
    (net (code "30") (name "/GPIO7") (class "Default")
      (node (ref "J2") (pin "10") (pinfunction "10_10") (pintype "passive"))
      (node (ref "u*2") (pin "11") (pinfunction "GPIO7/RTC_GPIO7/_TOUCH7/_ADC1_CH6_11") (pintype "passive"))
    )
    (net (code "31") (name "/GPIO8") (class "Default")
      (node (ref "J2") (pin "11") (pinfunction "11_11") (pintype "passive"))
      (node (ref "u*2") (pin "12") (pinfunction "GPIO8/RTC_GPIO8/__TOUCH8/_ADC1_CH7/_SUBSPICS1_12") (pintype "passive"))
    )
    (net (code "32") (name "/GPIO9") (class "Default")
      (node (ref "J2") (pin "12") (pinfunction "12_12") (pintype "passive"))
      (node (ref "u*2") (pin "13") (pinfunction "GPIO9/RTC_GPIO9/_TOUCH9/_ADC1_CH8/_FSPIHD/_SUBSPIHD_13") (pintype "passive"))
    )
    (net (code "33") (name "/GPIO10") (class "Default")
      (node (ref "J2") (pin "13") (pinfunction "13_13") (pintype "passive"))
      (node (ref "u*2") (pin "14") (pinfunction "GPIO10/RTC_GPIO10/_TOUCH10/_ADC1_CH9/_FSPICS0/_FSPIIO4/SUBSPICS0_14") (pintype "passive"))
    )
    (net (code "34") (name "/GPIO11") (class "Default")
      (node (ref "J2") (pin "14") (pinfunction "14_14") (pintype "passive"))
      (node (ref "u*2") (pin "15") (pinfunction "GPIO11/RTC_GPIO11/__TOUCH11/_ADC2_CH0/_FSPID/_FSPIIO5/_SUBSPID_15") (pintype "passive"))
    )
    (net (code "35") (name "/GPIO12") (class "Default")
      (node (ref "J2") (pin "15") (pinfunction "15_15") (pintype "passive"))
      (node (ref "u*2") (pin "16") (pinfunction "_GPIO12/RTC_GPIO12/__TOUCH12/_ADC2_CH1/_FSPICLK/_FSPIIO6/SUBSPICLK_16") (pintype "passive"))
    )
    (net (code "36") (name "/GPIO13") (class "Default")
      (node (ref "J2") (pin "16") (pinfunction "16_16") (pintype "passive"))
      (node (ref "u*2") (pin "17") (pinfunction "GPIO13/RTC_GPIO13/_TOUCH13/_ADC2_CH2/_FSPIQ/_FSPIIO7/_SUBSPIQ_17") (pintype "passive"))
    )
    (net (code "37") (name "/GPIO14") (class "Default")
      (node (ref "J2") (pin "17") (pinfunction "17_17") (pintype "passive"))
      (node (ref "u*2") (pin "18") (pinfunction "GPIO14/RTC_GPIO14/_TOUCH14/_ADC2_CH3/_FSPIWP/_FSPIDQS/SUBSPIWP_18") (pintype "passive"))
    )
    (net (code "38") (name "/GPIO15") (class "Default")
      (node (ref "J2") (pin "18") (pinfunction "18_18") (pintype "passive"))
      (node (ref "u*2") (pin "19") (pinfunction "GPIO15/RTC_GPIO15/__U0RTS/_ADC2_CH4/_XTAL_32K_P_19") (pintype "passive"))
    )
    (net (code "39") (name "/GPIO16") (class "Default")
      (node (ref "J2") (pin "19") (pinfunction "19_19") (pintype "passive"))
      (node (ref "u*2") (pin "20") (pinfunction "GPIO16/RTC_GPIO16/_U0CTS/_ADC2_CH5/_XTAL_32K_N_20") (pintype "passive"))
    )
    (net (code "40") (name "/GPIO17") (class "Default")
      (node (ref "J2") (pin "20") (pinfunction "20_20") (pintype "passive"))
      (node (ref "u*2") (pin "21") (pinfunction "GPIO17/RTC_GPIO17/__U1TXD/_ADC2_CH6_21") (pintype "passive"))
    )
    (net (code "41") (name "/GPIO18") (class "Default")
      (node (ref "J2") (pin "21") (pinfunction "21_21") (pintype "passive"))
      (node (ref "u*2") (pin "22") (pinfunction "GPIO18/RTC_GPIO18/__U1RXD/_ADC2_CH7/_CLK_OUT3_22") (pintype "passive"))
    )
    (net (code "42") (name "/GPIO21") (class "Default")
      (node (ref "J1") (pin "19") (pinfunction "19_19") (pintype "passive"))
      (node (ref "u*2") (pin "25") (pinfunction "GPIO21/RTC_25") (pintype "passive"))
    )
    (net (code "43") (name "/GPIO26") (class "Default")
      (node (ref "J1") (pin "18") (pinfunction "18_18") (pintype "passive"))
      (node (ref "u*2") (pin "26") (pinfunction "GPIO26/SPICS1_26") (pintype "passive"))
    )
    (net (code "44") (name "/GPIO33") (class "Default")
      (node (ref "J1") (pin "17") (pinfunction "17_17") (pintype "passive"))
      (node (ref "u*2") (pin "28") (pinfunction "GPIO33/SPIIO4/_FSPIHD/_SUBSPIHD_28") (pintype "passive"))
    )
    (net (code "45") (name "/GPIO34") (class "Default")
      (node (ref "J1") (pin "16") (pinfunction "16_16") (pintype "passive"))
      (node (ref "u*2") (pin "29") (pinfunction "GPIO34_/SPIIO5/FSPICS0/_SUBSPICS0_29") (pintype "passive"))
    )
    (net (code "46") (name "/GPIO35") (class "Default")
      (node (ref "J1") (pin "15") (pinfunction "15_15") (pintype "passive"))
      (node (ref "u*2") (pin "31") (pinfunction "GPIO35//SPIIO6/__FSPID/_SUBSPID_31") (pintype "passive"))
    )
    (net (code "47") (name "/GPIO36") (class "Default")
      (node (ref "J1") (pin "14") (pinfunction "14_14") (pintype "passive"))
      (node (ref "u*2") (pin "32") (pinfunction "GPIO36_/SPIIO7/FSPICLK/_SUBSPICLK_32") (pintype "passive"))
    )
    (net (code "48") (name "/GPIO37") (class "Default")
      (node (ref "J1") (pin "13") (pinfunction "13_13") (pintype "passive"))
      (node (ref "u*2") (pin "33") (pinfunction "GPIO37/SPIDQS/_-FSPIQ/_SUBSPIQ_33") (pintype "passive"))
    )
    (net (code "49") (name "/GPIO38") (class "Default")
      (node (ref "J1") (pin "12") (pinfunction "12_12") (pintype "passive"))
      (node (ref "u*2") (pin "34") (pinfunction "GPIO38/FSPIWP/_SUBSPIWP_34") (pintype "passive"))
    )
    (net (code "50") (name "/GPIO39") (class "Default")
      (node (ref "J1") (pin "11") (pinfunction "11_11") (pintype "passive"))
      (node (ref "u*2") (pin "35") (pinfunction "MTCK/_GPIO39/_CLK_OUT3/_SUBSPICS1_35") (pintype "passive"))
    )
    (net (code "51") (name "/GPIO40") (class "Default")
      (node (ref "J1") (pin "10") (pinfunction "10_10") (pintype "passive"))
      (node (ref "u*2") (pin "36") (pinfunction "MTDO/_GPIO40/_CLK_OUT2_36") (pintype "passive"))
    )
    (net (code "52") (name "/GPIO41") (class "Default")
      (node (ref "J1") (pin "9") (pinfunction "9_9") (pintype "passive"))
      (node (ref "u*2") (pin "37") (pinfunction "MTDI/_GPIO41/_CLK_OUT1_37") (pintype "passive"))
    )
    (net (code "53") (name "/GPIO42") (class "Default")
      (node (ref "J1") (pin "8") (pinfunction "8_8") (pintype "passive"))
      (node (ref "u*2") (pin "38") (pinfunction "MTMS/_GPIO42_38") (pintype "passive"))
    )
    (net (code "54") (name "/GPIO45") (class "Default")
      (node (ref "J1") (pin "5") (pinfunction "5_5") (pintype "passive"))
      (node (ref "u*2") (pin "41") (pinfunction "GPIO45_41") (pintype "passive"))
    )
    (net (code "55") (name "/GPIO46") (class "Default")
      (node (ref "J1") (pin "4") (pinfunction "4_4") (pintype "passive"))
      (node (ref "u*2") (pin "44") (pinfunction "GPIO46_44") (pintype "passive"))
    )
    (net (code "56") (name "/GPIO47") (class "Default")
      (node (ref "J1") (pin "23") (pinfunction "23_23") (pintype "passive"))
      (node (ref "u*2") (pin "27") (pinfunction "GPIO46/SPICLK_P_DIFF/_SUBSPICLK_P_DIFF_27") (pintype "passive"))
    )
    (net (code "57") (name "/GPIO48") (class "Default")
      (node (ref "J1") (pin "22") (pinfunction "22_22") (pintype "passive"))
      (node (ref "u*2") (pin "30") (pinfunction "GPIO48_/_SPICLK_N_DIFF/_SUBSPICLK_N_DIFF_30") (pintype "passive"))
    )
    (net (code "59") (name "/RTS_FTDI") (class "Default")
      (node (ref "Q1") (pin "2") (pinfunction "E_2") (pintype "passive"))
      (node (ref "R18") (pin "1") (pinfunction "1_1") (pintype "passive"))
      (node (ref "U*1") (pin "19") (pinfunction "~{RTS}_19") (pintype "passive"))
    )
    (net (code "60") (name "/RXD_FTDI") (class "Default")
      (node (ref "R22") (pin "2") (pinfunction "2_2") (pintype "passive"))
      (node (ref "U*1") (pin "1") (pinfunction "RXD_1") (pintype "passive"))
    )
    (net (code "61") (name "/TXD_FTDI") (class "Default")
      (node (ref "R20") (pin "2") (pinfunction "2_2") (pintype "passive"))
      (node (ref "U*1") (pin "17") (pinfunction "TXD_17") (pintype "passive"))
    )
    (net (code "62") (name "/U0RXD") (class "Default")
      (node (ref "J1") (pin "6") (pinfunction "6_6") (pintype "passive"))
      (node (ref "R20") (pin "1") (pinfunction "1_1") (pintype "passive"))
      (node (ref "u*2") (pin "40") (pinfunction "U0RXD/_GPIO44/_CLK_OUT2_40") (pintype "passive"))
    )
    (net (code "63") (name "/U0TXD") (class "Default")
      (node (ref "J1") (pin "7") (pinfunction "7_7") (pintype "passive"))
      (node (ref "R22") (pin "1") (pinfunction "1_1") (pintype "passive"))
      (node (ref "u*2") (pin "39") (pinfunction "U0TXD/_GPIO43/_CLK_OUT1_39") (pintype "passive"))
    )
    (net (code "64") (name "/VBUS_SENSE") (class "Default")
      (node (ref "R11") (pin "1") (pinfunction "1_1") (pintype "passive"))
      (node (ref "R8") (pin "1") (pinfunction "1_1") (pintype "passive"))
      (node (ref "U*1") (pin "16") (pinfunction "CBUS3_16") (pintype "passive"))
    )
    (net (code "65") (name "GND") (class "Default")
      (node (ref "C11") (pin "1") (pinfunction "1_1") (pintype "passive"))
      (node (ref "C12") (pin "1") (pinfunction "1_1") (pintype "passive"))
      (node (ref "C13") (pin "1") (pinfunction "1_1") (pintype "passive"))
      (node (ref "C17") (pin "1") (pinfunction "1_1") (pintype "passive"))
      (node (ref "D1") (pin "1") (pinfunction "1_1") (pintype "passive"))
      (node (ref "D2") (pin "1") (pinfunction "1_1") (pintype "passive"))
      (node (ref "D3") (pin "1") (pinfunction "1_1") (pintype "passive"))
      (node (ref "D4") (pin "1") (pinfunction "1_1") (pintype "passive"))
      (node (ref "D6") (pin "1") (pinfunction "1_1") (pintype "passive"))
      (node (ref "D7") (pin "1") (pinfunction "1_1") (pintype "passive"))
      (node (ref "D8") (pin "1") (pinfunction "1_1") (pintype "passive"))
      (node (ref "J*1") (pin "A1B12") (pinfunction "GND_A1B12_A1B12") (pintype "passive"))
      (node (ref "J*1") (pin "B1A12") (pinfunction "GND_B1A12_B1A12") (pintype "passive"))
      (node (ref "J*1") (pin "S1") (pinfunction "SHIELD_1_S1") (pintype "passive"))
      (node (ref "J*1") (pin "S2") (pinfunction "SHIELD_2_S2") (pintype "passive"))
      (node (ref "J*1") (pin "S3") (pinfunction "SHIELD_3_S3") (pintype "passive"))
      (node (ref "J*1") (pin "S4") (pinfunction "SHIELD_4_S4") (pintype "passive"))
      (node (ref "J*2") (pin "A1B12") (pinfunction "GND_A1B12_A1B12") (pintype "passive"))
      (node (ref "J*2") (pin "B1A12") (pinfunction "GND_B1A12_B1A12") (pintype "passive"))
      (node (ref "J*2") (pin "S1") (pinfunction "SHIELD_1_S1") (pintype "passive"))
      (node (ref "J*2") (pin "S2") (pinfunction "SHIELD_2_S2") (pintype "passive"))
      (node (ref "J*2") (pin "S3") (pinfunction "SHIELD_3_S3") (pintype "passive"))
      (node (ref "J*2") (pin "S4") (pinfunction "SHIELD_4_S4") (pintype "passive"))
      (node (ref "J1") (pin "1") (pinfunction "1_1") (pintype "passive"))
      (node (ref "J1") (pin "2") (pinfunction "2_2") (pintype "passive"))
      (node (ref "J1") (pin "24") (pinfunction "24_24") (pintype "passive"))
      (node (ref "J2") (pin "1") (pinfunction "1_1") (pintype "passive"))
      (node (ref "J2") (pin "2") (pinfunction "2_2") (pintype "passive"))
      (node (ref "J2") (pin "22") (pinfunction "22_22") (pintype "passive"))
      (node (ref "J2") (pin "23") (pinfunction "23_23") (pintype "passive"))
      (node (ref "R10") (pin "2") (pinfunction "2_2") (pintype "passive"))
      (node (ref "R11") (pin "2") (pinfunction "2_2") (pintype "passive"))
      (node (ref "R12") (pin "1") (pinfunction "1_1") (pintype "passive"))
      (node (ref "R13") (pin "1") (pinfunction "1_1") (pintype "passive"))
      (node (ref "R14") (pin "1") (pinfunction "1_1") (pintype "passive"))
      (node (ref "R15") (pin "1") (pinfunction "1_1") (pintype "passive"))
      (node (ref "SW1") (pin "3") (pinfunction "3_3") (pintype "passive"))
      (node (ref "SW1") (pin "4") (pinfunction "4_4") (pintype "passive"))
      (node (ref "SW2") (pin "3") (pinfunction "3_3") (pintype "passive"))
      (node (ref "SW2") (pin "4") (pinfunction "4_4") (pintype "passive"))
      (node (ref "U*1") (pin "13") (pinfunction "GND_13") (pintype "passive"))
      (node (ref "U*1") (pin "21") (pinfunction "GND_21") (pintype "passive"))
      (node (ref "U*1") (pin "3") (pinfunction "GND_3") (pintype "passive"))
      (node (ref "U1") (pin "2") (pinfunction "GND_2") (pintype "power_in"))
      (node (ref "U1") (pin "4") (pinfunction "GND_4") (pintype "power_in"))
      (node (ref "c1") (pin "1") (pinfunction "1_1") (pintype "passive"))
      (node (ref "c10") (pin "1") (pinfunction "1_1") (pintype "passive"))
      (node (ref "c14") (pin "1") (pinfunction "1_1") (pintype "passive"))
      (node (ref "c15") (pin "1") (pinfunction "1_1") (pintype "passive"))
      (node (ref "c16") (pin "1") (pinfunction "1_1") (pintype "passive"))
      (node (ref "c2") (pin "1") (pinfunction "1_1") (pintype "passive"))
      (node (ref "c3") (pin "1") (pinfunction "1_1") (pintype "passive"))
      (node (ref "c4") (pin "1") (pinfunction "1_1") (pintype "passive"))
      (node (ref "c5") (pin "1") (pinfunction "1_1") (pintype "passive"))
      (node (ref "c6") (pin "1") (pinfunction "1_1") (pintype "passive"))
      (node (ref "c7") (pin "2") (pinfunction "2_2") (pintype "passive"))
      (node (ref "c8") (pin "1") (pinfunction "1_1") (pintype "passive"))
      (node (ref "c9") (pin "1") (pinfunction "1_1") (pintype "passive"))
      (node (ref "u*2") (pin "1") (pinfunction "GND_01_1") (pintype "passive"))
      (node (ref "u*2") (pin "2") (pinfunction "GND_02_2") (pintype "passive"))
      (node (ref "u*2") (pin "42") (pinfunction "GND_42") (pintype "passive"))
      (node (ref "u*2") (pin "43") (pinfunction "GND_43") (pintype "passive"))
      (node (ref "u*2") (pin "46") (pinfunction "GND_46_46") (pintype "passive"))
      (node (ref "u*2") (pin "47") (pinfunction "GND_47_47") (pintype "passive"))
      (node (ref "u*2") (pin "48") (pinfunction "GND_48_48") (pintype "passive"))
      (node (ref "u*2") (pin "49") (pinfunction "GND_49_49") (pintype "passive"))
      (node (ref "u*2") (pin "50") (pinfunction "GND_50_50") (pintype "passive"))
      (node (ref "u*2") (pin "51") (pinfunction "GND_51_51") (pintype "passive"))
      (node (ref "u*2") (pin "52") (pinfunction "GND_52_52") (pintype "passive"))
      (node (ref "u*2") (pin "53") (pinfunction "GND_53_53") (pintype "passive"))
      (node (ref "u*2") (pin "54") (pinfunction "GND_54_54") (pintype "passive"))
      (node (ref "u*2") (pin "55") (pinfunction "GND_55_55") (pintype "passive"))
      (node (ref "u*2") (pin "56") (pinfunction "GND_56_56") (pintype "passive"))
      (node (ref "u*2") (pin "57") (pinfunction "GND_57_57") (pintype "passive"))
      (node (ref "u*2") (pin "58") (pinfunction "GND_58_58") (pintype "passive"))
      (node (ref "u*2") (pin "59") (pinfunction "GND_59_59") (pintype "passive"))
      (node (ref "u*2") (pin "60") (pinfunction "GND_60_60") (pintype "passive"))
      (node (ref "u*2") (pin "61") (pinfunction "GND_61_61") (pintype "passive"))
      (node (ref "u*2") (pin "62") (pinfunction "GND_62_62") (pintype "passive"))
      (node (ref "u*2") (pin "63") (pinfunction "GND_63_63") (pintype "passive"))
      (node (ref "u*2") (pin "64") (pinfunction "GND_64_64") (pintype "passive"))
      (node (ref "u*2") (pin "65") (pinfunction "GND_65_65") (pintype "passive"))
      (node (ref "u*2") (pin "66") (pinfunction "GND_66_66") (pintype "passive"))
      (node (ref "u*2") (pin "67") (pinfunction "GND_67_67") (pintype "passive"))
      (node (ref "u*2") (pin "68") (pinfunction "GND_68_68") (pintype "passive"))
      (node (ref "u*2") (pin "69") (pinfunction "GND_69_69") (pintype "passive"))
      (node (ref "u*2") (pin "70") (pinfunction "GND_70_70") (pintype "passive"))
      (node (ref "u*2") (pin "71") (pinfunction "GND_71_71") (pintype "passive"))
      (node (ref "u*2") (pin "72") (pinfunction "GND_72_72") (pintype "passive"))
      (node (ref "u*2") (pin "73") (pinfunction "GND_73_73") (pintype "passive"))
    )
    (net (code "66") (name "Net-(D1-Pad2)") (class "Default")
      (node (ref "D1") (pin "2") (pinfunction "2_2") (pintype "passive"))
      (node (ref "R6") (pin "1") (pinfunction "1_1") (pintype "passive"))
    )
    (net (code "67") (name "Net-(D5-Pad2)") (class "Default")
      (node (ref "D5") (pin "2") (pinfunction "2_2") (pintype "passive"))
      (node (ref "R9") (pin "1") (pinfunction "1_1") (pintype "passive"))
    )
    (net (code "68") (name "Net-(J*1-CC2)") (class "Default")
      (node (ref "J*1") (pin "B5") (pinfunction "CC2_B5") (pintype "passive"))
      (node (ref "R12") (pin "2") (pinfunction "2_2") (pintype "passive"))
    )
    (net (code "69") (name "Net-(J*1-CCI)") (class "Default")
      (node (ref "J*1") (pin "A5") (pinfunction "CCI_A5") (pintype "passive"))
      (node (ref "R13") (pin "2") (pinfunction "2_2") (pintype "passive"))
    )
    (net (code "70") (name "Net-(J*2-CC2)") (class "Default")
      (node (ref "J*2") (pin "B5") (pinfunction "CC2_B5") (pintype "passive"))
      (node (ref "R14") (pin "2") (pinfunction "2_2") (pintype "passive"))
    )
    (net (code "71") (name "Net-(J*2-CCI)") (class "Default")
      (node (ref "J*2") (pin "A5") (pinfunction "CCI_A5") (pintype "passive"))
      (node (ref "R15") (pin "2") (pinfunction "2_2") (pintype "passive"))
    )
    (net (code "72") (name "Net-(Q1-B)") (class "Default")
      (node (ref "Q1") (pin "1") (pinfunction "B_1") (pintype "passive"))
      (node (ref "R16") (pin "2") (pinfunction "2_2") (pintype "passive"))
    )
    (net (code "73") (name "Net-(Q2-B)") (class "Default")
      (node (ref "Q2") (pin "1") (pinfunction "B_1") (pintype "passive"))
      (node (ref "R18") (pin "2") (pinfunction "2_2") (pintype "passive"))
    )
    (net (code "74") (name "Net-(U*1-CBUS0)") (class "Default")
      (node (ref "R10") (pin "1") (pinfunction "1_1") (pintype "passive"))
      (node (ref "U*1") (pin "15") (pinfunction "CBUS0_15") (pintype "passive"))
    )
    (net (code "75") (name "unconnected-(J*1-PadB8)") (class "Default")
      (node (ref "J*1") (pin "B8") (pinfunction "B8_B8") (pintype "passive+no_connect"))
    )
    (net (code "76") (name "unconnected-(J*1-SBU1-PadA8)") (class "Default")
      (node (ref "J*1") (pin "A8") (pinfunction "SBU1_A8") (pintype "passive+no_connect"))
    )
    (net (code "77") (name "unconnected-(J*2-PadB8)") (class "Default")
      (node (ref "J*2") (pin "B8") (pinfunction "B8_B8") (pintype "passive+no_connect"))
    )
    (net (code "78") (name "unconnected-(J*2-SBU1-PadA8)") (class "Default")
      (node (ref "J*2") (pin "A8") (pinfunction "SBU1_A8") (pintype "passive+no_connect"))
    )
    (net (code "79") (name "unconnected-(J2-Pad24)") (class "Default")
      (node (ref "J2") (pin "24") (pinfunction "24_24") (pintype "passive+no_connect"))
    )
    (net (code "80") (name "unconnected-(U*1-CBUS1-Pad14)") (class "Default")
      (node (ref "U*1") (pin "14") (pinfunction "CBUS1_14") (pintype "passive+no_connect"))
    )
    (net (code "81") (name "unconnected-(U*1-CBUS2-Pad7)") (class "Default")
      (node (ref "U*1") (pin "7") (pinfunction "CBUS2_7") (pintype "passive+no_connect"))
    )
    (net (code "82") (name "unconnected-(U*1-~{CTS}-Pad6)") (class "Default")
      (node (ref "U*1") (pin "6") (pinfunction "~{CTS}_6") (pintype "passive+no_connect"))
    )
    (net (code "83") (name "unconnected-(U*1-~{DCD}-Pad5)") (class "Default")
      (node (ref "U*1") (pin "5") (pinfunction "~{DCD}_5") (pintype "passive+no_connect"))
    )
    (net (code "84") (name "unconnected-(U*1-~{DSR}-Pad4)") (class "Default")
      (node (ref "U*1") (pin "4") (pinfunction "~{DSR}_4") (pintype "passive+no_connect"))
    )
    (net (code "85") (name "unconnected-(U*1-~{RI}-Pad2)") (class "Default")
      (node (ref "U*1") (pin "2") (pinfunction "~{RI}_2") (pintype "passive+no_connect"))
    )
  )
)
